# Peripherals.net
KiCad netlist of a schematic drawn in Altium Designer
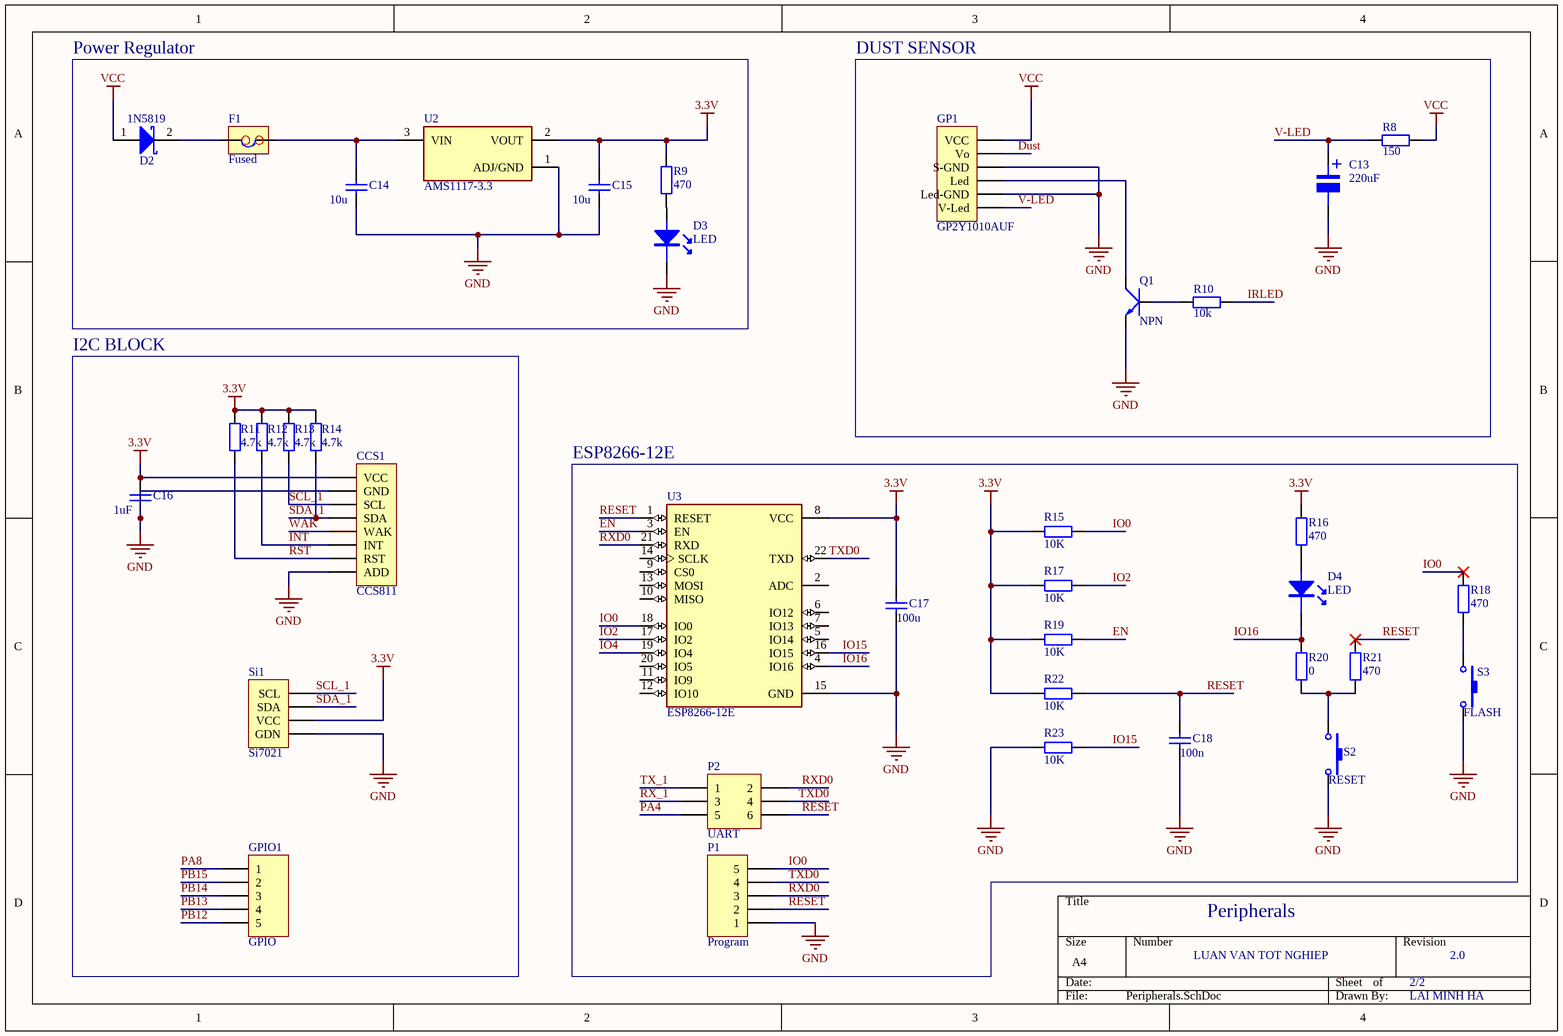
[diagram p0: Peripherals.SchDoc]

(export (version "E")
  (design (tool "Eeschema 10.0.6"))
  (components
    (comp (ref "C13")
      (value "220uF")
      (footprint "tu nhom 8 (e)")
      (description "Dán")
      (libsource (lib "Tu dien") (part "Tu Nhom 220uF 10V"))
    )
    (comp (ref "C14")
      (value "10u")
      (footprint "C0805")
      (description "Capacitor")
      (fields (field (name "PUBLISHER") "Altium Limited"))
      (libsource (lib "My Library") (part "CapSMD"))
    )
    (comp (ref "C15")
      (value "10u")
      (footprint "C0805")
      (description "Capacitor")
      (fields (field (name "PUBLISHER") "Altium Limited"))
      (libsource (lib "My Library") (part "CapSMD"))
    )
    (comp (ref "C16")
      (value "1uF")
      (footprint "C0805")
      (description "Capacitor")
      (fields (field (name "PUBLISHER") "Altium Limited"))
      (libsource (lib "My Library") (part "CapSMD"))
    )
    (comp (ref "C17")
      (value "100u")
      (footprint "C0805")
      (description "100n")
      (fields (field (name "PUBLISHER") "Altium Limited"))
      (libsource (lib "My Library") (part "CapSMD"))
    )
    (comp (ref "C18")
      (value "100n")
      (footprint "C0805")
      (fields (field (name "PUBLISHER") "Altium Limited"))
      (libsource (lib "My Library") (part "CapSMD"))
    )
    (comp (ref "CCS1")
      (value "CCS811")
      (footprint "HDR1X8")
      (description "Header, 8-Pin")
      (fields (field (name "PUBLISHER") "Altium Limited"))
      (libsource (lib "My Library") (part "Header 8"))
    )
    (comp (ref "D2") (value "1N5819") (footprint "SOD123") (libsource (lib "sch") (part "Diode Schottky")))
    (comp (ref "D3") (value "LED") (footprint "LED 0805") (libsource (lib "Cty1") (part "LED")))
    (comp (ref "D4") (value "LED") (footprint "LED 0805") (libsource (lib "Cty1") (part "LED")))
    (comp (ref "F1") (value "Fused") (footprint "HDR1X2H") (libsource (lib "My Library") (part "FuseNote2")))
    (comp (ref "FLASH")
      (value "S3")
      (footprint "SW-SMD")
      (description "Switch")
      (fields (field (name "PUBLISHER") "Altium Limited"))
      (libsource (lib "My Library") (part "SW-SMD"))
    )
    (comp (ref "GP1")
      (value "GP2Y1010AUF")
      (footprint "HDR1X6")
      (description "Header, 6-Pin")
      (fields (field (name "PUBLISHER") "Altium Limited"))
      (libsource (lib "My Library") (part "Header 6"))
    )
    (comp (ref "GPIO1")
      (value "GPIO")
      (footprint "HDR1X5")
      (description "Header, 5-Pin")
      (fields (field (name "PUBLISHER") "Altium Limited"))
      (libsource (lib "Miscellaneous Connectors") (part "Header 5"))
    )
    (comp (ref "P1")
      (value "Program")
      (footprint "HDR1X5H")
      (description "Header, 5-Pin, Right Angle")
      (fields (field (name "PUBLISHER") "Altium Limited"))
      (libsource (lib "My Library") (part "Header 5H"))
    )
    (comp (ref "P2")
      (value "UART")
      (footprint "HDR2X3")
      (description "Header, 3-Pin, Dual row")
      (fields (field (name "PUBLISHER") "Altium Limited"))
      (libsource (lib "My Library") (part "Header 3X2"))
    )
    (comp (ref "Q1")
      (value "NPN")
      (footprint "SOT23-231")
      (description "NPN 600mW, ECB")
      (libsource (lib "LIBRARY1") (part "2N222"))
    )
    (comp (ref "R8")
      (value "150")
      (footprint "DIEN TRO 0805")
      (description "Resistor SMD 0805")
      (fields (field (name "Comment") "R0805") (field (name "PUBLISHER") "Altium Limited"))
      (libsource (lib "") (part "R0805_1"))
    )
    (comp (ref "R9")
      (value "470")
      (footprint "tro smd 0805")
      (description "Dán")
      (libsource (lib "Dien Tro") (part "Tro 0805 1% 82k"))
    )
    (comp (ref "R10")
      (value "10k")
      (footprint "DIEN TRO 0805")
      (description "Resistor SMD 0805")
      (fields (field (name "Comment") "R0805") (field (name "PUBLISHER") "Altium Limited"))
      (libsource (lib "") (part "R0805_1"))
    )
    (comp (ref "R11")
      (value "4.7k")
      (footprint "DIEN TRO 0805")
      (description "Resistor SMD 0805")
      (fields (field (name "Comment") "R0805") (field (name "PUBLISHER") "Altium Limited"))
      (libsource (lib "My Library") (part "R0805"))
    )
    (comp (ref "R12")
      (value "4.7k")
      (footprint "DIEN TRO 0805")
      (description "Resistor SMD 0805")
      (fields (field (name "Comment") "R0805") (field (name "PUBLISHER") "Altium Limited"))
      (libsource (lib "My Library") (part "R0805"))
    )
    (comp (ref "R13")
      (value "4.7k")
      (footprint "DIEN TRO 0805")
      (description "Resistor SMD 0805")
      (fields (field (name "Comment") "R0805") (field (name "PUBLISHER") "Altium Limited"))
      (libsource (lib "My Library") (part "R0805"))
    )
    (comp (ref "R14")
      (value "4.7k")
      (footprint "DIEN TRO 0805")
      (description "Resistor SMD 0805")
      (fields (field (name "Comment") "R0805") (field (name "PUBLISHER") "Altium Limited"))
      (libsource (lib "My Library") (part "R0805"))
    )
    (comp (ref "R15")
      (value "10K")
      (footprint "tro smd 0805")
      (description "Dán")
      (libsource (lib "Dien Tro") (part "Tro 0805 1% 82k"))
    )
    (comp (ref "R16")
      (value "470")
      (footprint "tro smd 0805")
      (description "Dán")
      (libsource (lib "Dien Tro") (part "Tro 0805 1% 82k"))
    )
    (comp (ref "R17")
      (value "10K")
      (footprint "tro smd 0805")
      (description "Dán")
      (libsource (lib "Dien Tro") (part "Tro 0805 1% 82k"))
    )
    (comp (ref "R18")
      (value "470")
      (footprint "tro smd 0805")
      (description "Dán")
      (libsource (lib "Dien Tro") (part "Tro 0805 1% 82k"))
    )
    (comp (ref "R19")
      (value "10K")
      (footprint "tro smd 0805")
      (description "Dán")
      (libsource (lib "Dien Tro") (part "Tro 0805 1% 82k"))
    )
    (comp (ref "R20")
      (value "0")
      (footprint "tro smd 0805")
      (description "Dán")
      (libsource (lib "Dien Tro") (part "Tro 0805 1% 82k"))
    )
    (comp (ref "R21")
      (value "470")
      (footprint "tro smd 0805")
      (description "Dán")
      (libsource (lib "Dien Tro") (part "Tro 0805 1% 82k"))
    )
    (comp (ref "R22")
      (value "10K")
      (footprint "tro smd 0805")
      (description "Dán")
      (libsource (lib "Dien Tro") (part "Tro 0805 1% 82k"))
    )
    (comp (ref "R23")
      (value "10K")
      (footprint "tro smd 0805")
      (description "Dán")
      (libsource (lib "Dien Tro") (part "Tro 0805 1% 82k"))
    )
    (comp (ref "S2")
      (value "RESET")
      (footprint "SW-SMD")
      (description "Switch")
      (fields (field (name "PUBLISHER") "Altium Limited"))
      (libsource (lib "My Library") (part "SW-SMD"))
    )
    (comp (ref "Si1")
      (value "Si7021")
      (footprint "Header 4")
      (description "Header, 4-Pin")
      (fields (field (name "PUBLISHER") "Altium Limited"))
      (libsource (lib "hphonglib") (part "Header 4"))
    )
    (comp (ref "U2")
      (value "AMS1117-3.3")
      (footprint "SOT-223")
      (description "Sot223/Pkg 1-Amp 3.3-Volt Low Drop Out Voltage Regulatator")
      (fields (field (name "MF") "Advanced Monolithic Systems"))
      (libsource (lib "AMS1117-3.3") (part "AMS1117-3.3"))
    )
    (comp (ref "U3")
      (value "ESP8266-12E")
      (footprint "XCVR_ESP8266-12E/ESP-12E")
      (fields (field (name "MP") "ESP8266-12E/ESP-12E") (field (name "MF") "AI-Thinker"))
      (libsource (lib "ESP8266-12E_ESP-12E") (part "ESP8266-12E/ESP-12E"))
    )
  )
  (nets
    (net (code "1") (name "/Dust") (class "Default")
      (node (ref "GP1") (pin "5") (pinfunction "Vo_5") (pintype "passive"))
    )
    (net (code "2") (name "/EN") (class "Default")
      (node (ref "R19") (pin "2") (pinfunction "2_2") (pintype "passive"))
      (node (ref "U3") (pin "3") (pinfunction "EN_3") (pintype "bidirectional"))
    )
    (net (code "3") (name "/INT") (class "Default")
      (node (ref "CCS1") (pin "6") (pinfunction "INT_6") (pintype "passive"))
      (node (ref "R12") (pin "2") (pinfunction "2_2") (pintype "passive"))
    )
    (net (code "4") (name "/IO0") (class "Default")
      (node (ref "P1") (pin "5") (pinfunction "5_5") (pintype "passive"))
      (node (ref "R15") (pin "2") (pinfunction "2_2") (pintype "passive"))
      (node (ref "R18") (pin "2") (pinfunction "2_2") (pintype "passive"))
      (node (ref "U3") (pin "18") (pinfunction "IO0_18") (pintype "bidirectional"))
    )
    (net (code "5") (name "/IO2") (class "Default")
      (node (ref "R17") (pin "2") (pinfunction "2_2") (pintype "passive"))
      (node (ref "U3") (pin "17") (pinfunction "IO2_17") (pintype "bidirectional"))
    )
    (net (code "6") (name "/IO4") (class "Default")
      (node (ref "U3") (pin "19") (pinfunction "IO4_19") (pintype "bidirectional"))
    )
    (net (code "7") (name "/IO15") (class "Default")
      (node (ref "R23") (pin "2") (pinfunction "2_2") (pintype "passive"))
      (node (ref "U3") (pin "16") (pinfunction "IO15_16") (pintype "bidirectional"))
    )
    (net (code "8") (name "/IO16") (class "Default")
      (node (ref "D4") (pin "2") (pinfunction "2_2") (pintype "passive"))
      (node (ref "R20") (pin "2") (pinfunction "2_2") (pintype "passive"))
      (node (ref "U3") (pin "4") (pinfunction "IO16_4") (pintype "bidirectional"))
    )
    (net (code "9") (name "/IRLED") (class "Default")
      (node (ref "R10") (pin "1") (pinfunction "1_1") (pintype "passive"))
    )
    (net (code "10") (name "/PA4") (class "Default")
      (node (ref "P2") (pin "5") (pinfunction "5_5") (pintype "passive"))
    )
    (net (code "11") (name "/PA8") (class "Default")
      (node (ref "GPIO1") (pin "1") (pinfunction "1_1") (pintype "passive"))
    )
    (net (code "12") (name "/PB12") (class "Default")
      (node (ref "GPIO1") (pin "5") (pinfunction "5_5") (pintype "passive"))
    )
    (net (code "13") (name "/PB13") (class "Default")
      (node (ref "GPIO1") (pin "4") (pinfunction "4_4") (pintype "passive"))
    )
    (net (code "14") (name "/PB14") (class "Default")
      (node (ref "GPIO1") (pin "3") (pinfunction "3_3") (pintype "passive"))
    )
    (net (code "15") (name "/PB15") (class "Default")
      (node (ref "GPIO1") (pin "2") (pinfunction "2_2") (pintype "passive"))
    )
    (net (code "16") (name "/RESET") (class "Default")
      (node (ref "C18") (pin "2") (pinfunction "2_2") (pintype "passive"))
      (node (ref "P1") (pin "2") (pinfunction "2_2") (pintype "passive"))
      (node (ref "P2") (pin "6") (pinfunction "6_6") (pintype "passive"))
      (node (ref "R21") (pin "2") (pinfunction "2_2") (pintype "passive"))
      (node (ref "R22") (pin "2") (pinfunction "2_2") (pintype "passive"))
      (node (ref "U3") (pin "1") (pinfunction "RESET_1") (pintype "bidirectional"))
    )
    (net (code "17") (name "/RST") (class "Default")
      (node (ref "CCS1") (pin "7") (pinfunction "RST_7") (pintype "passive"))
      (node (ref "R11") (pin "2") (pinfunction "2_2") (pintype "passive"))
    )
    (net (code "18") (name "/RXD0") (class "Default")
      (node (ref "P1") (pin "3") (pinfunction "3_3") (pintype "passive"))
      (node (ref "P2") (pin "2") (pinfunction "2_2") (pintype "passive"))
      (node (ref "U3") (pin "21") (pinfunction "RXD_21") (pintype "bidirectional"))
    )
    (net (code "19") (name "/RX_1") (class "Default")
      (node (ref "P2") (pin "3") (pinfunction "3_3") (pintype "passive"))
    )
    (net (code "20") (name "/SCL_1") (class "Default")
      (node (ref "CCS1") (pin "3") (pinfunction "SCL_3") (pintype "passive"))
      (node (ref "R13") (pin "2") (pinfunction "2_2") (pintype "passive"))
      (node (ref "Si1") (pin "4") (pinfunction "SCL_4") (pintype "passive"))
    )
    (net (code "21") (name "/SDA_1") (class "Default")
      (node (ref "CCS1") (pin "4") (pinfunction "SDA_4") (pintype "passive"))
      (node (ref "R14") (pin "2") (pinfunction "2_2") (pintype "passive"))
      (node (ref "Si1") (pin "3") (pinfunction "SDA_3") (pintype "passive"))
    )
    (net (code "22") (name "/TXD0") (class "Default")
      (node (ref "P1") (pin "4") (pinfunction "4_4") (pintype "passive"))
      (node (ref "P2") (pin "4") (pinfunction "4_4") (pintype "passive"))
      (node (ref "U3") (pin "22") (pinfunction "TXD_22") (pintype "bidirectional"))
    )
    (net (code "23") (name "/TX_1") (class "Default")
      (node (ref "P2") (pin "1") (pinfunction "1_1") (pintype "passive"))
    )
    (net (code "24") (name "/V-LED") (class "Default")
      (node (ref "C13") (pin "1") (pinfunction "1_1") (pintype "passive"))
      (node (ref "GP1") (pin "1") (pinfunction "V-Led_1") (pintype "passive"))
      (node (ref "R8") (pin "2") (pinfunction "2_2") (pintype "passive"))
    )
    (net (code "25") (name "/WAK") (class "Default")
      (node (ref "CCS1") (pin "5") (pinfunction "WAK_5") (pintype "passive"))
    )
    (net (code "26") (name "3.3V") (class "Default")
      (node (ref "C15") (pin "2") (pinfunction "2_2") (pintype "passive"))
      (node (ref "C16") (pin "2") (pinfunction "2_2") (pintype "passive"))
      (node (ref "C17") (pin "2") (pinfunction "2_2") (pintype "passive"))
      (node (ref "CCS1") (pin "1") (pinfunction "VCC_1") (pintype "passive"))
      (node (ref "R11") (pin "1") (pinfunction "1_1") (pintype "passive"))
      (node (ref "R12") (pin "1") (pinfunction "1_1") (pintype "passive"))
      (node (ref "R13") (pin "1") (pinfunction "1_1") (pintype "passive"))
      (node (ref "R14") (pin "1") (pinfunction "1_1") (pintype "passive"))
      (node (ref "R15") (pin "1") (pinfunction "1_1") (pintype "passive"))
      (node (ref "R16") (pin "2") (pinfunction "2_2") (pintype "passive"))
      (node (ref "R17") (pin "1") (pinfunction "1_1") (pintype "passive"))
      (node (ref "R19") (pin "1") (pinfunction "1_1") (pintype "passive"))
      (node (ref "R22") (pin "1") (pinfunction "1_1") (pintype "passive"))
      (node (ref "R9") (pin "2") (pinfunction "2_2") (pintype "passive"))
      (node (ref "Si1") (pin "2") (pinfunction "VCC_2") (pintype "passive"))
      (node (ref "U2") (pin "2") (pinfunction "VOUT_2") (pintype "power_in"))
      (node (ref "U3") (pin "8") (pinfunction "VCC_8") (pintype "power_in"))
    )
    (net (code "27") (name "GND") (class "Default")
      (node (ref "C13") (pin "2") (pinfunction "2_2") (pintype "passive"))
      (node (ref "C14") (pin "1") (pinfunction "1_1") (pintype "passive"))
      (node (ref "C15") (pin "1") (pinfunction "1_1") (pintype "passive"))
      (node (ref "C16") (pin "1") (pinfunction "1_1") (pintype "passive"))
      (node (ref "C17") (pin "1") (pinfunction "1_1") (pintype "passive"))
      (node (ref "C18") (pin "1") (pinfunction "1_1") (pintype "passive"))
      (node (ref "CCS1") (pin "2") (pinfunction "GND_2") (pintype "passive"))
      (node (ref "CCS1") (pin "8") (pinfunction "ADD_8") (pintype "passive"))
      (node (ref "D3") (pin "2") (pinfunction "2_2") (pintype "passive"))
      (node (ref "FLASH") (pin "2") (pinfunction "2_2") (pintype "passive"))
      (node (ref "GP1") (pin "2") (pinfunction "Led-GND_2") (pintype "passive"))
      (node (ref "GP1") (pin "4") (pinfunction "S-GND_4") (pintype "passive"))
      (node (ref "P1") (pin "1") (pinfunction "1_1") (pintype "passive"))
      (node (ref "Q1") (pin "1") (pinfunction "E_1") (pintype "passive"))
      (node (ref "R23") (pin "1") (pinfunction "1_1") (pintype "passive"))
      (node (ref "S2") (pin "2") (pinfunction "2_2") (pintype "passive"))
      (node (ref "Si1") (pin "1") (pinfunction "GDN_1") (pintype "passive"))
      (node (ref "U2") (pin "1") (pinfunction "ADJ/GND_1") (pintype "power_in"))
      (node (ref "U3") (pin "15") (pinfunction "GND_15") (pintype "power_in"))
    )
    (net (code "28") (name "Net-(D2-4)") (class "Default")
      (node (ref "D2") (pin "2") (pinfunction "4_2") (pintype "passive"))
      (node (ref "F1") (pin "1") (pinfunction "1_1") (pintype "passive"))
    )
    (net (code "29") (name "Net-(D3-Pad1)") (class "Default")
      (node (ref "D3") (pin "1") (pinfunction "1_1") (pintype "passive"))
      (node (ref "R9") (pin "1") (pinfunction "1_1") (pintype "passive"))
    )
    (net (code "30") (name "Net-(D4-Pad1)") (class "Default")
      (node (ref "D4") (pin "1") (pinfunction "1_1") (pintype "passive"))
      (node (ref "R16") (pin "1") (pinfunction "1_1") (pintype "passive"))
    )
    (net (code "31") (name "Net-(FLASH-Pad1)") (class "Default")
      (node (ref "FLASH") (pin "1") (pinfunction "1_1") (pintype "passive"))
      (node (ref "R18") (pin "1") (pinfunction "1_1") (pintype "passive"))
    )
    (net (code "32") (name "Net-(GP1-Led)") (class "Default")
      (node (ref "GP1") (pin "3") (pinfunction "Led_3") (pintype "passive"))
      (node (ref "Q1") (pin "3") (pinfunction "C_3") (pintype "passive"))
    )
    (net (code "33") (name "Net-(Q1-B)") (class "Default")
      (node (ref "Q1") (pin "2") (pinfunction "B_2") (pintype "passive"))
      (node (ref "R10") (pin "2") (pinfunction "2_2") (pintype "passive"))
    )
    (net (code "34") (name "Net-(R20-Pad1)") (class "Default")
      (node (ref "R20") (pin "1") (pinfunction "1_1") (pintype "passive"))
      (node (ref "R21") (pin "1") (pinfunction "1_1") (pintype "passive"))
      (node (ref "S2") (pin "1") (pinfunction "1_1") (pintype "passive"))
    )
    (net (code "35") (name "Net-(U2-VIN)") (class "Default")
      (node (ref "C14") (pin "2") (pinfunction "2_2") (pintype "passive"))
      (node (ref "F1") (pin "2") (pinfunction "2_2") (pintype "passive"))
      (node (ref "U2") (pin "3") (pinfunction "VIN_3") (pintype "power_in"))
    )
    (net (code "36") (name "VCC") (class "Default")
      (node (ref "D2") (pin "1") (pinfunction "A_1") (pintype "passive"))
      (node (ref "GP1") (pin "6") (pinfunction "VCC_6") (pintype "passive"))
      (node (ref "R8") (pin "1") (pinfunction "1_1") (pintype "passive"))
    )
    (net (code "37") (name "unconnected-(U3-ADC-Pad2)") (class "Default")
      (node (ref "U3") (pin "2") (pinfunction "ADC_2") (pintype "passive"))
    )
    (net (code "38") (name "unconnected-(U3-CS0-Pad9)") (class "Default")
      (node (ref "U3") (pin "9") (pinfunction "CS0_9") (pintype "bidirectional"))
    )
    (net (code "39") (name "unconnected-(U3-IO5-Pad20)") (class "Default")
      (node (ref "U3") (pin "20") (pinfunction "IO5_20") (pintype "bidirectional"))
    )
    (net (code "40") (name "unconnected-(U3-IO9-Pad11)") (class "Default")
      (node (ref "U3") (pin "11") (pinfunction "IO9_11") (pintype "bidirectional"))
    )
    (net (code "41") (name "unconnected-(U3-IO10-Pad12)") (class "Default")
      (node (ref "U3") (pin "12") (pinfunction "IO10_12") (pintype "bidirectional"))
    )
    (net (code "42") (name "unconnected-(U3-IO12-Pad6)") (class "Default")
      (node (ref "U3") (pin "6") (pinfunction "IO12_6") (pintype "bidirectional"))
    )
    (net (code "43") (name "unconnected-(U3-IO13-Pad7)") (class "Default")
      (node (ref "U3") (pin "7") (pinfunction "IO13_7") (pintype "bidirectional"))
    )
    (net (code "44") (name "unconnected-(U3-IO14-Pad5)") (class "Default")
      (node (ref "U3") (pin "5") (pinfunction "IO14_5") (pintype "bidirectional"))
    )
    (net (code "45") (name "unconnected-(U3-MISO-Pad10)") (class "Default")
      (node (ref "U3") (pin "10") (pinfunction "MISO_10") (pintype "bidirectional"))
    )
    (net (code "46") (name "unconnected-(U3-MOSI-Pad13)") (class "Default")
      (node (ref "U3") (pin "13") (pinfunction "MOSI_13") (pintype "bidirectional"))
    )
    (net (code "47") (name "unconnected-(U3-SCLK-Pad14)") (class "Default")
      (node (ref "U3") (pin "14") (pinfunction "SCLK_14") (pintype "bidirectional"))
    )
  )
)
